# BATT_CONNECTOR_INVERSOR.net
KiCad netlist of a schematic drawn in EAGLE
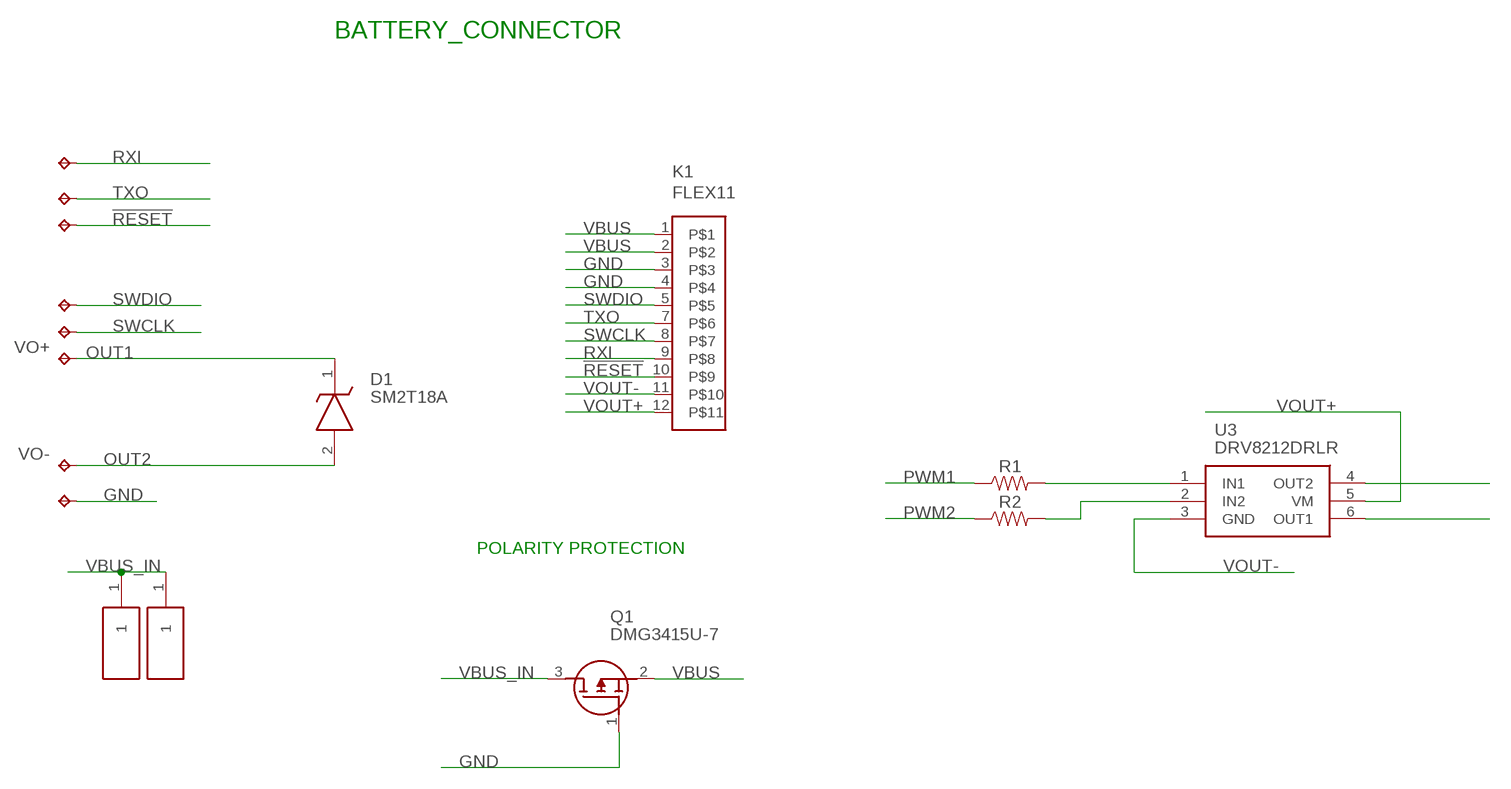
[diagram p0: schematic, sheet 1]

(export (version "E")
  (design (tool "Eeschema 10.0.6"))
  (components
    (comp (ref "!RESET")
      (value "TPB2,54")
      (footprint "eagle-import:B2,54")
      (libsource (lib "eagle-import") (part "TPB2,54"))
    )
    (comp (ref "D1")
      (value "SM2T18A")
      (footprint "eagle-import:SM2T18A")
      (fields (field (name "MOUSER_PART_NUMBER") "511-SM2T18A"))
      (libsource (lib "eagle-import") (part "SM2T18A"))
    )
    (comp (ref "GND")
      (value "TPB2,54")
      (footprint "eagle-import:B2,54")
      (libsource (lib "eagle-import") (part "TPB2,54"))
    )
    (comp (ref "H1")
      (value "S1761-42R")
      (footprint "eagle-import:S176142R")
      (fields (field (name "MOUSER_PART_NUMBER") "855-S1761-42R"))
      (libsource (lib "eagle-import") (part "S1761-42R"))
    )
    (comp (ref "H2")
      (value "S1761-42R")
      (footprint "eagle-import:S176142R")
      (fields (field (name "MOUSER_PART_NUMBER") "855-S1761-42R"))
      (libsource (lib "eagle-import") (part "S1761-42R"))
    )
    (comp (ref "K1")
      (value "FLEX11")
      (footprint "eagle-import:FLEX11")
      (libsource (lib "eagle-import") (part "FLEX11"))
    )
    (comp (ref "Q1")
      (value "DMG3415U-7")
      (footprint "eagle-import:SSM3J332RLFT")
      (fields
        (field (name "ARROW_PART_NUMBER") "SSM3J338R,LF")
        (field (name "MOUSER_PART_NUMBER") "757-SSM3J338RLF")
      )
      (libsource (lib "eagle-import") (part "SSM3J338R,LF"))
    )
    (comp (ref "R1")
      (value "RESISTOR0805")
      (footprint "eagle-import:0805")
      (libsource (lib "eagle-import") (part "RESISTOR0805"))
    )
    (comp (ref "R2")
      (value "RESISTOR0805")
      (footprint "eagle-import:0805")
      (libsource (lib "eagle-import") (part "RESISTOR0805"))
    )
    (comp (ref "RXI")
      (value "TPB2,54")
      (footprint "eagle-import:B2,54")
      (libsource (lib "eagle-import") (part "TPB2,54"))
    )
    (comp (ref "SWCLK")
      (value "TPB2,54")
      (footprint "eagle-import:B2,54")
      (libsource (lib "eagle-import") (part "TPB2,54"))
    )
    (comp (ref "SWDIO")
      (value "TPB2,54")
      (footprint "eagle-import:B2,54")
      (libsource (lib "eagle-import") (part "TPB2,54"))
    )
    (comp (ref "TXO")
      (value "TPB2,54")
      (footprint "eagle-import:B2,54")
      (libsource (lib "eagle-import") (part "TPB2,54"))
    )
    (comp (ref "U3")
      (value "DRV8212DRLR")
      (footprint "eagle-import:SOTFL50P160X60-6N")
      (fields (field (name "MOUSER_PART_NUMBER") "595-DRV8212DRLR"))
      (libsource (lib "eagle-import") (part "DRV8212DRLR"))
    )
    (comp (ref "VO+")
      (value "TPB2,54")
      (footprint "eagle-import:B2,54")
      (libsource (lib "eagle-import") (part "TPB2,54"))
    )
    (comp (ref "VO-")
      (value "TPB2,54")
      (footprint "eagle-import:B2,54")
      (libsource (lib "eagle-import") (part "TPB2,54"))
    )
  )
  (nets
    (net (code "1") (name "/GND") (class "Default")
      (node (ref "GND") (pin "TP") (pinfunction "TP_TP") (pintype "input"))
      (node (ref "K1") (pin "3") (pinfunction "P$3_3") (pintype "bidirectional"))
      (node (ref "K1") (pin "4") (pinfunction "P$4_4") (pintype "bidirectional"))
      (node (ref "Q1") (pin "1") (pinfunction "G_1") (pintype "bidirectional"))
    )
    (net (code "2") (name "/OUT1") (class "Default")
      (node (ref "D1") (pin "1") (pinfunction "K_1") (pintype "bidirectional"))
      (node (ref "U3") (pin "6") (pinfunction "OUT1_6") (pintype "bidirectional"))
      (node (ref "VO+") (pin "TP") (pinfunction "TP_TP") (pintype "input"))
    )
    (net (code "3") (name "/OUT2") (class "Default")
      (node (ref "D1") (pin "2") (pinfunction "A_2") (pintype "bidirectional"))
      (node (ref "U3") (pin "4") (pinfunction "OUT2_4") (pintype "bidirectional"))
      (node (ref "VO-") (pin "TP") (pinfunction "TP_TP") (pintype "input"))
    )
    (net (code "4") (name "/PWM1") (class "Default")
      (node (ref "R1") (pin "1") (pinfunction "1_1") (pintype "passive"))
    )
    (net (code "5") (name "/PWM2") (class "Default")
      (node (ref "R2") (pin "1") (pinfunction "1_1") (pintype "passive"))
    )
    (net (code "6") (name "/RXI") (class "Default")
      (node (ref "K1") (pin "9") (pinfunction "P$8_9") (pintype "bidirectional"))
      (node (ref "RXI") (pin "TP") (pinfunction "TP_TP") (pintype "input"))
    )
    (net (code "7") (name "/SWCLK") (class "Default")
      (node (ref "K1") (pin "8") (pinfunction "P$7_8") (pintype "bidirectional"))
      (node (ref "SWCLK") (pin "TP") (pinfunction "TP_TP") (pintype "input"))
    )
    (net (code "8") (name "/SWDIO") (class "Default")
      (node (ref "K1") (pin "5") (pinfunction "P$5_5") (pintype "bidirectional"))
      (node (ref "SWDIO") (pin "TP") (pinfunction "TP_TP") (pintype "input"))
    )
    (net (code "9") (name "/TXO") (class "Default")
      (node (ref "K1") (pin "7") (pinfunction "P$6_7") (pintype "bidirectional"))
      (node (ref "TXO") (pin "TP") (pinfunction "TP_TP") (pintype "input"))
    )
    (net (code "10") (name "/VBUS") (class "Default")
      (node (ref "K1") (pin "1") (pinfunction "P$1_1") (pintype "bidirectional"))
      (node (ref "K1") (pin "2") (pinfunction "P$2_2") (pintype "bidirectional"))
      (node (ref "Q1") (pin "2") (pinfunction "S_2") (pintype "bidirectional"))
    )
    (net (code "11") (name "/VBUS_IN") (class "Default")
      (node (ref "H1") (pin "1") (pinfunction "1_1") (pintype "bidirectional"))
      (node (ref "H2") (pin "1") (pinfunction "1_1") (pintype "bidirectional"))
      (node (ref "Q1") (pin "3") (pinfunction "D_3") (pintype "bidirectional"))
    )
    (net (code "12") (name "/VOUT+") (class "Default")
      (node (ref "K1") (pin "12") (pinfunction "P$11_12") (pintype "bidirectional"))
      (node (ref "U3") (pin "5") (pinfunction "VM_5") (pintype "bidirectional"))
    )
    (net (code "13") (name "/VOUT-") (class "Default")
      (node (ref "K1") (pin "11") (pinfunction "P$10_11") (pintype "bidirectional"))
      (node (ref "U3") (pin "3") (pinfunction "GND_3") (pintype "bidirectional"))
    )
    (net (code "14") (name "/~{RESET}") (class "Default")
      (node (ref "!RESET") (pin "TP") (pinfunction "TP_TP") (pintype "input"))
      (node (ref "K1") (pin "10") (pinfunction "P$9_10") (pintype "bidirectional"))
    )
    (net (code "15") (name "Net-(U3-IN1)") (class "Default")
      (node (ref "R1") (pin "2") (pinfunction "2_2") (pintype "passive"))
      (node (ref "U3") (pin "1") (pinfunction "IN1_1") (pintype "bidirectional"))
    )
    (net (code "16") (name "Net-(U3-IN2)") (class "Default")
      (node (ref "R2") (pin "2") (pinfunction "2_2") (pintype "passive"))
      (node (ref "U3") (pin "2") (pinfunction "IN2_2") (pintype "bidirectional"))
    )
  )
)
